# xns-ip67-ESP12.net
KiCad netlist of a schematic drawn in EAGLE
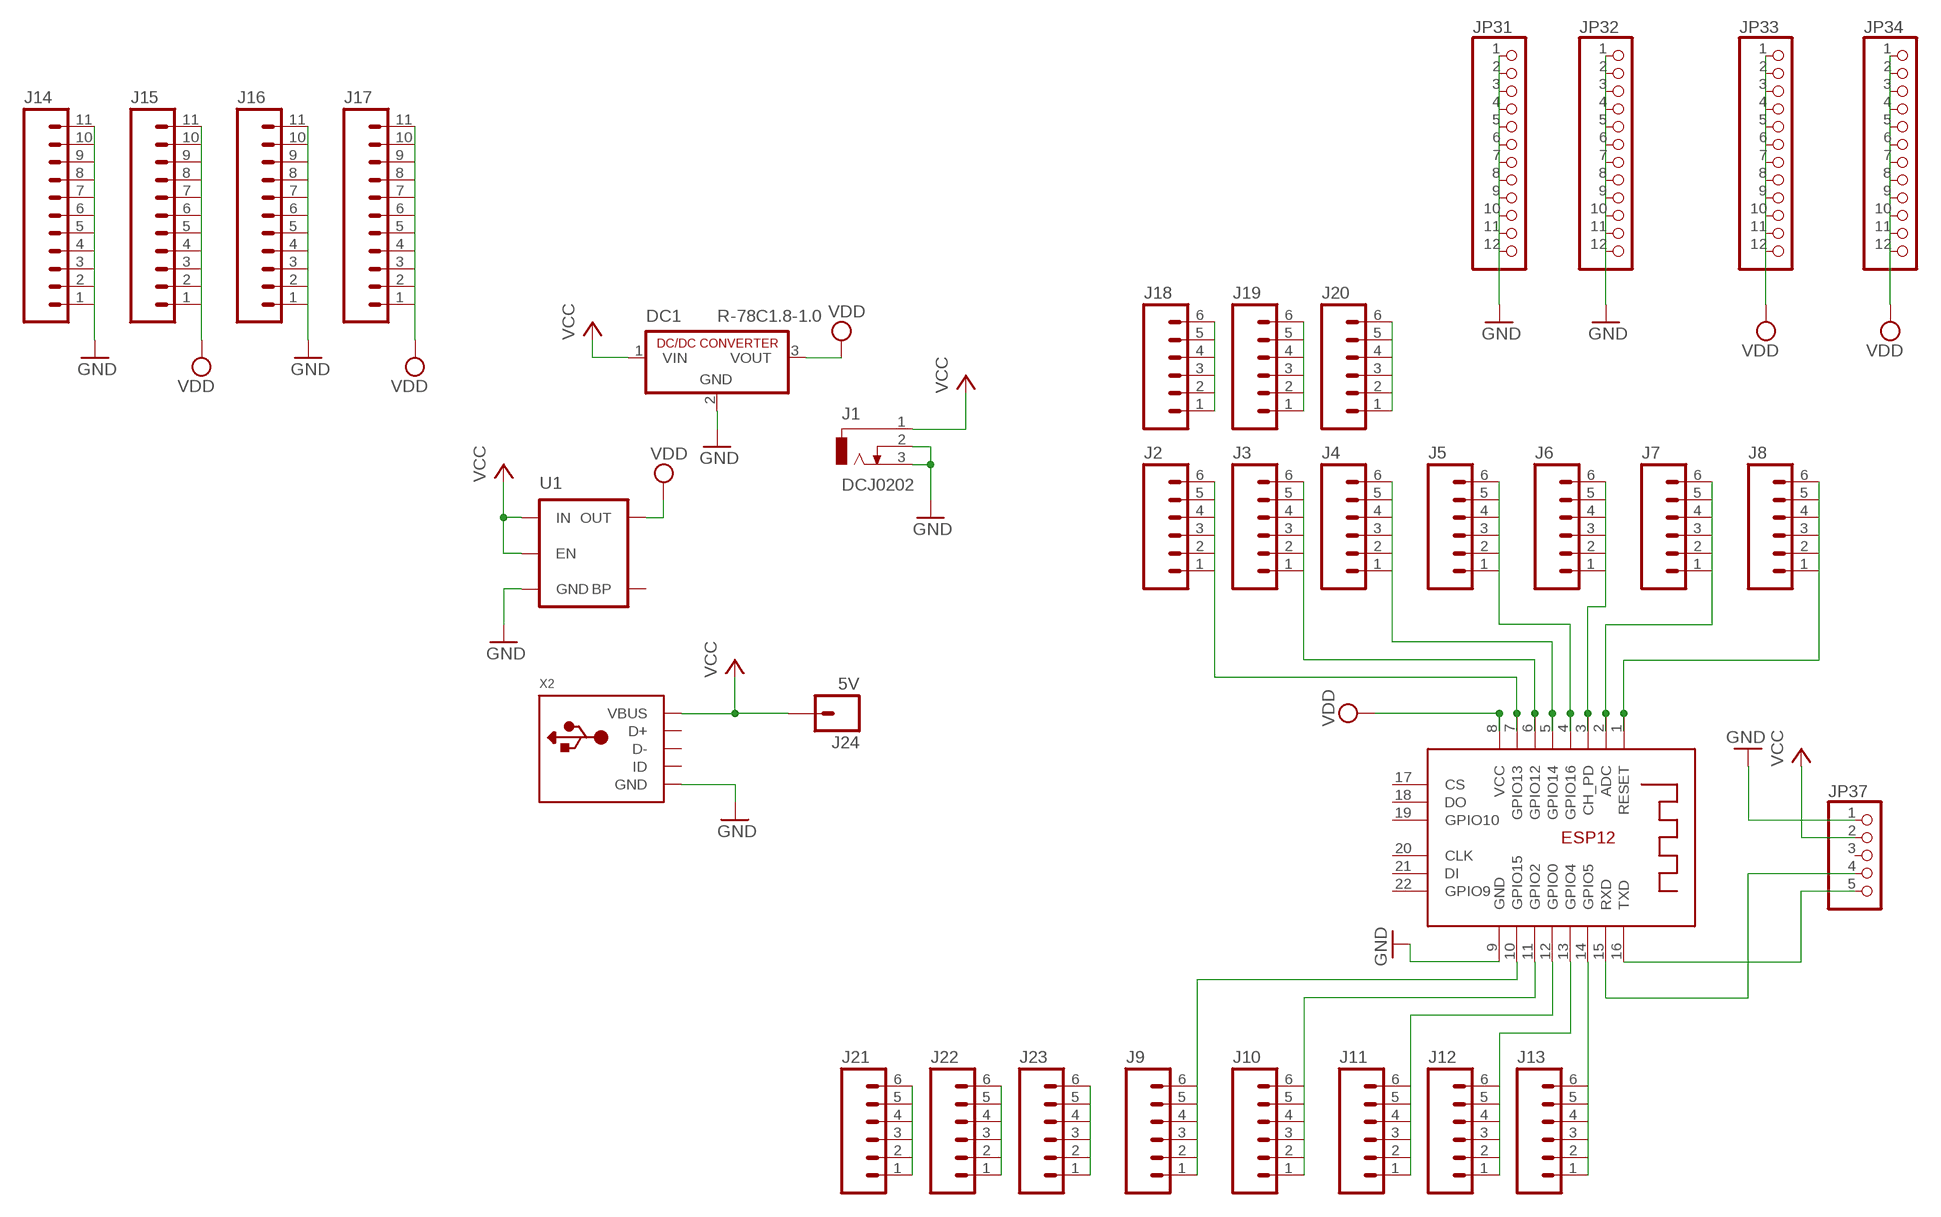
[diagram p0: schematic, sheet 1, part 1 of 2]
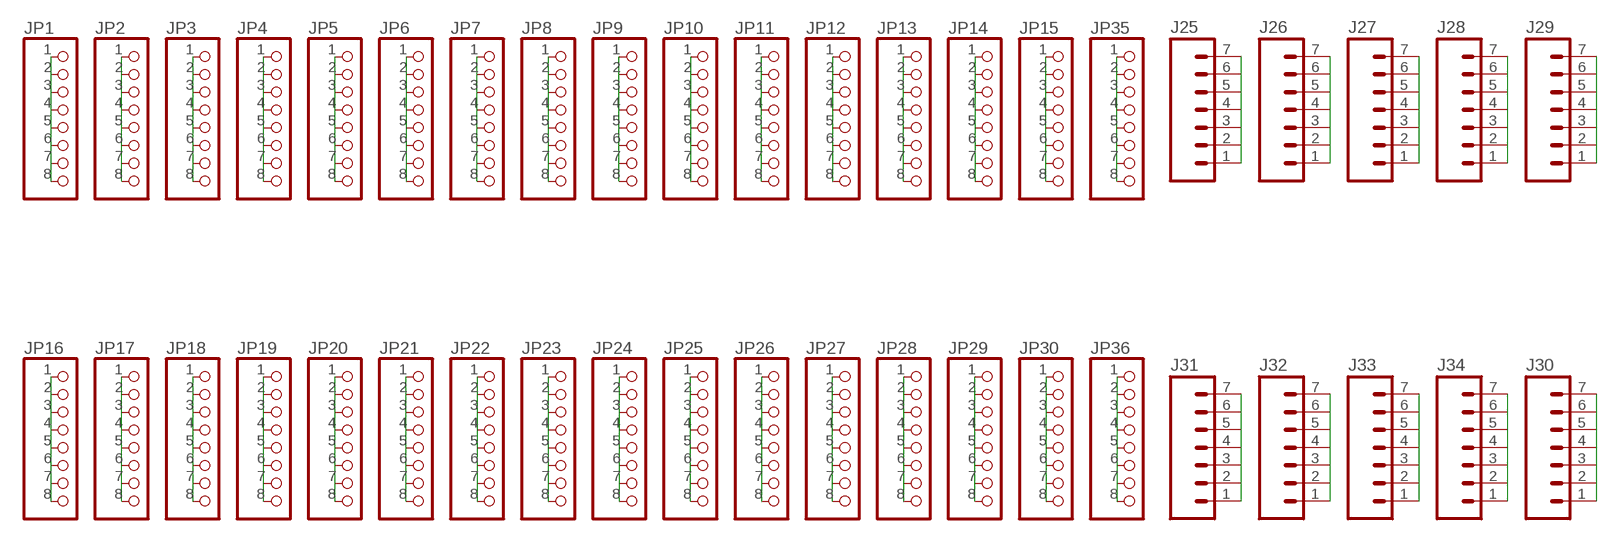
[diagram p1: schematic, sheet 1, part 2 of 2]

(export (version "E")
  (design (tool "Eeschema 10.0.6"))
  (components
    (comp (ref "DC1")
      (value "R-78C1.8-1.0")
      (footprint "eagle-import:SIP3")
      (libsource (lib "eagle-import") (part "R-78C-1.01.8"))
    )
    (comp (ref "J1")
      (value "DCJ0202")
      (footprint "eagle-import:DCJ0202")
      (libsource (lib "eagle-import") (part "DCJ0202"))
    )
    (comp (ref "J2")
      (value "M06NO_SILK_FEMALE_PTH")
      (footprint "eagle-import:1X06_NO_SILK")
      (libsource (lib "eagle-import") (part "M06NO_SILK_FEMALE_PTH"))
    )
    (comp (ref "J3")
      (value "M06NO_SILK_FEMALE_PTH")
      (footprint "eagle-import:1X06_NO_SILK")
      (libsource (lib "eagle-import") (part "M06NO_SILK_FEMALE_PTH"))
    )
    (comp (ref "J4")
      (value "M06NO_SILK_FEMALE_PTH")
      (footprint "eagle-import:1X06_NO_SILK")
      (libsource (lib "eagle-import") (part "M06NO_SILK_FEMALE_PTH"))
    )
    (comp (ref "J5")
      (value "M06NO_SILK_FEMALE_PTH")
      (footprint "eagle-import:1X06_NO_SILK")
      (libsource (lib "eagle-import") (part "M06NO_SILK_FEMALE_PTH"))
    )
    (comp (ref "J6")
      (value "M06NO_SILK_FEMALE_PTH")
      (footprint "eagle-import:1X06_NO_SILK")
      (libsource (lib "eagle-import") (part "M06NO_SILK_FEMALE_PTH"))
    )
    (comp (ref "J7")
      (value "M06NO_SILK_FEMALE_PTH")
      (footprint "eagle-import:1X06_NO_SILK")
      (libsource (lib "eagle-import") (part "M06NO_SILK_FEMALE_PTH"))
    )
    (comp (ref "J8")
      (value "M06NO_SILK_FEMALE_PTH")
      (footprint "eagle-import:1X06_NO_SILK")
      (libsource (lib "eagle-import") (part "M06NO_SILK_FEMALE_PTH"))
    )
    (comp (ref "J9")
      (value "M06NO_SILK_FEMALE_PTH")
      (footprint "eagle-import:1X06_NO_SILK")
      (libsource (lib "eagle-import") (part "M06NO_SILK_FEMALE_PTH"))
    )
    (comp (ref "J10")
      (value "M06NO_SILK_FEMALE_PTH")
      (footprint "eagle-import:1X06_NO_SILK")
      (libsource (lib "eagle-import") (part "M06NO_SILK_FEMALE_PTH"))
    )
    (comp (ref "J11")
      (value "M06NO_SILK_FEMALE_PTH")
      (footprint "eagle-import:1X06_NO_SILK")
      (libsource (lib "eagle-import") (part "M06NO_SILK_FEMALE_PTH"))
    )
    (comp (ref "J12")
      (value "M06NO_SILK_FEMALE_PTH")
      (footprint "eagle-import:1X06_NO_SILK")
      (libsource (lib "eagle-import") (part "M06NO_SILK_FEMALE_PTH"))
    )
    (comp (ref "J13")
      (value "M06NO_SILK_FEMALE_PTH")
      (footprint "eagle-import:1X06_NO_SILK")
      (libsource (lib "eagle-import") (part "M06NO_SILK_FEMALE_PTH"))
    )
    (comp (ref "J14")
      (value "M111X11_NO_SILK")
      (footprint "eagle-import:1X11_NO_SILK")
      (libsource (lib "eagle-import") (part "M111X11_NO_SILK"))
    )
    (comp (ref "J15")
      (value "M111X11_NO_SILK")
      (footprint "eagle-import:1X11_NO_SILK")
      (libsource (lib "eagle-import") (part "M111X11_NO_SILK"))
    )
    (comp (ref "J16")
      (value "M111X11_NO_SILK")
      (footprint "eagle-import:1X11_NO_SILK")
      (libsource (lib "eagle-import") (part "M111X11_NO_SILK"))
    )
    (comp (ref "J17")
      (value "M111X11_NO_SILK")
      (footprint "eagle-import:1X11_NO_SILK")
      (libsource (lib "eagle-import") (part "M111X11_NO_SILK"))
    )
    (comp (ref "J18")
      (value "M06NO_SILK_FEMALE_PTH")
      (footprint "eagle-import:1X06_NO_SILK")
      (libsource (lib "eagle-import") (part "M06NO_SILK_FEMALE_PTH"))
    )
    (comp (ref "J19")
      (value "M06NO_SILK_FEMALE_PTH")
      (footprint "eagle-import:1X06_NO_SILK")
      (libsource (lib "eagle-import") (part "M06NO_SILK_FEMALE_PTH"))
    )
    (comp (ref "J20")
      (value "M06NO_SILK_FEMALE_PTH")
      (footprint "eagle-import:1X06_NO_SILK")
      (libsource (lib "eagle-import") (part "M06NO_SILK_FEMALE_PTH"))
    )
    (comp (ref "J21")
      (value "M06NO_SILK_FEMALE_PTH")
      (footprint "eagle-import:1X06_NO_SILK")
      (libsource (lib "eagle-import") (part "M06NO_SILK_FEMALE_PTH"))
    )
    (comp (ref "J22")
      (value "M06NO_SILK_FEMALE_PTH")
      (footprint "eagle-import:1X06_NO_SILK")
      (libsource (lib "eagle-import") (part "M06NO_SILK_FEMALE_PTH"))
    )
    (comp (ref "J23")
      (value "M06NO_SILK_FEMALE_PTH")
      (footprint "eagle-import:1X06_NO_SILK")
      (libsource (lib "eagle-import") (part "M06NO_SILK_FEMALE_PTH"))
    )
    (comp (ref "J24")
      (value "5V")
      (footprint "eagle-import:1X01_NO_SILK")
      (libsource (lib "eagle-import") (part "M01PTH_NO_SILK_YES_STOP"))
    )
    (comp (ref "J25")
      (value "M07NO_SILK")
      (footprint "eagle-import:1X07_NO_SILK")
      (libsource (lib "eagle-import") (part "M07NO_SILK"))
    )
    (comp (ref "J26")
      (value "M07NO_SILK")
      (footprint "eagle-import:1X07_NO_SILK")
      (libsource (lib "eagle-import") (part "M07NO_SILK"))
    )
    (comp (ref "J27")
      (value "M07NO_SILK")
      (footprint "eagle-import:1X07_NO_SILK")
      (libsource (lib "eagle-import") (part "M07NO_SILK"))
    )
    (comp (ref "J28")
      (value "M07NO_SILK")
      (footprint "eagle-import:1X07_NO_SILK")
      (libsource (lib "eagle-import") (part "M07NO_SILK"))
    )
    (comp (ref "J29")
      (value "M07NO_SILK")
      (footprint "eagle-import:1X07_NO_SILK")
      (libsource (lib "eagle-import") (part "M07NO_SILK"))
    )
    (comp (ref "J30")
      (value "M07NO_SILK")
      (footprint "eagle-import:1X07_NO_SILK")
      (libsource (lib "eagle-import") (part "M07NO_SILK"))
    )
    (comp (ref "J31")
      (value "M07NO_SILK")
      (footprint "eagle-import:1X07_NO_SILK")
      (libsource (lib "eagle-import") (part "M07NO_SILK"))
    )
    (comp (ref "J32")
      (value "M07NO_SILK")
      (footprint "eagle-import:1X07_NO_SILK")
      (libsource (lib "eagle-import") (part "M07NO_SILK"))
    )
    (comp (ref "J33")
      (value "M07NO_SILK")
      (footprint "eagle-import:1X07_NO_SILK")
      (libsource (lib "eagle-import") (part "M07NO_SILK"))
    )
    (comp (ref "J34")
      (value "M07NO_SILK")
      (footprint "eagle-import:1X07_NO_SILK")
      (libsource (lib "eagle-import") (part "M07NO_SILK"))
    )
    (comp (ref "JP1")
      (value "PINHD-1X8CLEANBIG")
      (footprint "eagle-import:1X08-CLEANBIG")
      (libsource (lib "eagle-import") (part "PINHD-1X8CLEANBIG"))
    )
    (comp (ref "JP2")
      (value "PINHD-1X8CLEANBIG")
      (footprint "eagle-import:1X08-CLEANBIG")
      (libsource (lib "eagle-import") (part "PINHD-1X8CLEANBIG"))
    )
    (comp (ref "JP3")
      (value "PINHD-1X8CLEANBIG")
      (footprint "eagle-import:1X08-CLEANBIG")
      (libsource (lib "eagle-import") (part "PINHD-1X8CLEANBIG"))
    )
    (comp (ref "JP4")
      (value "PINHD-1X8CLEANBIG")
      (footprint "eagle-import:1X08-CLEANBIG")
      (libsource (lib "eagle-import") (part "PINHD-1X8CLEANBIG"))
    )
    (comp (ref "JP5")
      (value "PINHD-1X8CLEANBIG")
      (footprint "eagle-import:1X08-CLEANBIG")
      (libsource (lib "eagle-import") (part "PINHD-1X8CLEANBIG"))
    )
    (comp (ref "JP6")
      (value "PINHD-1X8CLEANBIG")
      (footprint "eagle-import:1X08-CLEANBIG")
      (libsource (lib "eagle-import") (part "PINHD-1X8CLEANBIG"))
    )
    (comp (ref "JP7")
      (value "PINHD-1X8CLEANBIG")
      (footprint "eagle-import:1X08-CLEANBIG")
      (libsource (lib "eagle-import") (part "PINHD-1X8CLEANBIG"))
    )
    (comp (ref "JP8")
      (value "PINHD-1X8CLEANBIG")
      (footprint "eagle-import:1X08-CLEANBIG")
      (libsource (lib "eagle-import") (part "PINHD-1X8CLEANBIG"))
    )
    (comp (ref "JP9")
      (value "PINHD-1X8CLEANBIG")
      (footprint "eagle-import:1X08-CLEANBIG")
      (libsource (lib "eagle-import") (part "PINHD-1X8CLEANBIG"))
    )
    (comp (ref "JP10")
      (value "PINHD-1X8CLEANBIG")
      (footprint "eagle-import:1X08-CLEANBIG")
      (libsource (lib "eagle-import") (part "PINHD-1X8CLEANBIG"))
    )
    (comp (ref "JP11")
      (value "PINHD-1X8CLEANBIG")
      (footprint "eagle-import:1X08-CLEANBIG")
      (libsource (lib "eagle-import") (part "PINHD-1X8CLEANBIG"))
    )
    (comp (ref "JP12")
      (value "PINHD-1X8CLEANBIG")
      (footprint "eagle-import:1X08-CLEANBIG")
      (libsource (lib "eagle-import") (part "PINHD-1X8CLEANBIG"))
    )
    (comp (ref "JP13")
      (value "PINHD-1X8CLEANBIG")
      (footprint "eagle-import:1X08-CLEANBIG")
      (libsource (lib "eagle-import") (part "PINHD-1X8CLEANBIG"))
    )
    (comp (ref "JP14")
      (value "PINHD-1X8CLEANBIG")
      (footprint "eagle-import:1X08-CLEANBIG")
      (libsource (lib "eagle-import") (part "PINHD-1X8CLEANBIG"))
    )
    (comp (ref "JP15")
      (value "PINHD-1X8CLEANBIG")
      (footprint "eagle-import:1X08-CLEANBIG")
      (libsource (lib "eagle-import") (part "PINHD-1X8CLEANBIG"))
    )
    (comp (ref "JP16")
      (value "PINHD-1X8CLEANBIG")
      (footprint "eagle-import:1X08-CLEANBIG")
      (libsource (lib "eagle-import") (part "PINHD-1X8CLEANBIG"))
    )
    (comp (ref "JP17")
      (value "PINHD-1X8CLEANBIG")
      (footprint "eagle-import:1X08-CLEANBIG")
      (libsource (lib "eagle-import") (part "PINHD-1X8CLEANBIG"))
    )
    (comp (ref "JP18")
      (value "PINHD-1X8CLEANBIG")
      (footprint "eagle-import:1X08-CLEANBIG")
      (libsource (lib "eagle-import") (part "PINHD-1X8CLEANBIG"))
    )
    (comp (ref "JP19")
      (value "PINHD-1X8CLEANBIG")
      (footprint "eagle-import:1X08-CLEANBIG")
      (libsource (lib "eagle-import") (part "PINHD-1X8CLEANBIG"))
    )
    (comp (ref "JP20")
      (value "PINHD-1X8CLEANBIG")
      (footprint "eagle-import:1X08-CLEANBIG")
      (libsource (lib "eagle-import") (part "PINHD-1X8CLEANBIG"))
    )
    (comp (ref "JP21")
      (value "PINHD-1X8CLEANBIG")
      (footprint "eagle-import:1X08-CLEANBIG")
      (libsource (lib "eagle-import") (part "PINHD-1X8CLEANBIG"))
    )
    (comp (ref "JP22")
      (value "PINHD-1X8CLEANBIG")
      (footprint "eagle-import:1X08-CLEANBIG")
      (libsource (lib "eagle-import") (part "PINHD-1X8CLEANBIG"))
    )
    (comp (ref "JP23")
      (value "PINHD-1X8CLEANBIG")
      (footprint "eagle-import:1X08-CLEANBIG")
      (libsource (lib "eagle-import") (part "PINHD-1X8CLEANBIG"))
    )
    (comp (ref "JP24")
      (value "PINHD-1X8CLEANBIG")
      (footprint "eagle-import:1X08-CLEANBIG")
      (libsource (lib "eagle-import") (part "PINHD-1X8CLEANBIG"))
    )
    (comp (ref "JP25")
      (value "PINHD-1X8CLEANBIG")
      (footprint "eagle-import:1X08-CLEANBIG")
      (libsource (lib "eagle-import") (part "PINHD-1X8CLEANBIG"))
    )
    (comp (ref "JP26")
      (value "PINHD-1X8CLEANBIG")
      (footprint "eagle-import:1X08-CLEANBIG")
      (libsource (lib "eagle-import") (part "PINHD-1X8CLEANBIG"))
    )
    (comp (ref "JP27")
      (value "PINHD-1X8CLEANBIG")
      (footprint "eagle-import:1X08-CLEANBIG")
      (libsource (lib "eagle-import") (part "PINHD-1X8CLEANBIG"))
    )
    (comp (ref "JP28")
      (value "PINHD-1X8CLEANBIG")
      (footprint "eagle-import:1X08-CLEANBIG")
      (libsource (lib "eagle-import") (part "PINHD-1X8CLEANBIG"))
    )
    (comp (ref "JP29")
      (value "PINHD-1X8CLEANBIG")
      (footprint "eagle-import:1X08-CLEANBIG")
      (libsource (lib "eagle-import") (part "PINHD-1X8CLEANBIG"))
    )
    (comp (ref "JP30")
      (value "PINHD-1X8CLEANBIG")
      (footprint "eagle-import:1X08-CLEANBIG")
      (libsource (lib "eagle-import") (part "PINHD-1X8CLEANBIG"))
    )
    (comp (ref "JP31")
      (value "HEADER-1X12")
      (footprint "eagle-import:1X12_ROUND")
      (libsource (lib "eagle-import") (part "HEADER-1X12"))
    )
    (comp (ref "JP32")
      (value "HEADER-1X12")
      (footprint "eagle-import:1X12_ROUND")
      (libsource (lib "eagle-import") (part "HEADER-1X12"))
    )
    (comp (ref "JP33")
      (value "HEADER-1X12")
      (footprint "eagle-import:1X12_ROUND")
      (libsource (lib "eagle-import") (part "HEADER-1X12"))
    )
    (comp (ref "JP34")
      (value "HEADER-1X12")
      (footprint "eagle-import:1X12_ROUND")
      (libsource (lib "eagle-import") (part "HEADER-1X12"))
    )
    (comp (ref "JP35")
      (value "PINHD-1X8CLEANBIG")
      (footprint "eagle-import:1X08-CLEANBIG")
      (libsource (lib "eagle-import") (part "PINHD-1X8CLEANBIG"))
    )
    (comp (ref "JP36")
      (value "PINHD-1X8CLEANBIG")
      (footprint "eagle-import:1X08-CLEANBIG")
      (libsource (lib "eagle-import") (part "PINHD-1X8CLEANBIG"))
    )
    (comp (ref "JP37")
      (value "PINHD-1X5")
      (footprint "eagle-import:1X05")
      (libsource (lib "eagle-import") (part "PINHD-1X5"))
    )
    (comp (ref "U1")
      (value "MIC52053.3V")
      (footprint "eagle-import:SOT23-5")
      (libsource (lib "eagle-import") (part "MIC52053.3V"))
    )
    (comp (ref "X1")
      (value "ESP-12E")
      (footprint "eagle-import:ESP-12E")
      (libsource (lib "eagle-import") (part "ESP-12E"))
    )
    (comp (ref "X2")
      (value "USBMICRO_20329")
      (footprint "eagle-import:4UCONN_20329")
      (libsource (lib "eagle-import") (part "USBMICRO_20329"))
    )
  )
  (nets
    (net (code "1") (name "GND") (class "Default")
      (node (ref "DC1") (pin "2") (pinfunction "GND_2") (pintype "passive"))
      (node (ref "J1") (pin "2") (pinfunction "2_2") (pintype "passive"))
      (node (ref "J1") (pin "3") (pinfunction "3_3") (pintype "passive"))
      (node (ref "J14") (pin "1") (pinfunction "1_1") (pintype "passive"))
      (node (ref "J14") (pin "10") (pinfunction "10_10") (pintype "passive"))
      (node (ref "J14") (pin "11") (pinfunction "11_11") (pintype "passive"))
      (node (ref "J14") (pin "2") (pinfunction "2_2") (pintype "passive"))
      (node (ref "J14") (pin "3") (pinfunction "3_3") (pintype "passive"))
      (node (ref "J14") (pin "4") (pinfunction "4_4") (pintype "passive"))
      (node (ref "J14") (pin "5") (pinfunction "5_5") (pintype "passive"))
      (node (ref "J14") (pin "6") (pinfunction "6_6") (pintype "passive"))
      (node (ref "J14") (pin "7") (pinfunction "7_7") (pintype "passive"))
      (node (ref "J14") (pin "8") (pinfunction "8_8") (pintype "passive"))
      (node (ref "J14") (pin "9") (pinfunction "9_9") (pintype "passive"))
      (node (ref "J16") (pin "1") (pinfunction "1_1") (pintype "passive"))
      (node (ref "J16") (pin "10") (pinfunction "10_10") (pintype "passive"))
      (node (ref "J16") (pin "11") (pinfunction "11_11") (pintype "passive"))
      (node (ref "J16") (pin "2") (pinfunction "2_2") (pintype "passive"))
      (node (ref "J16") (pin "3") (pinfunction "3_3") (pintype "passive"))
      (node (ref "J16") (pin "4") (pinfunction "4_4") (pintype "passive"))
      (node (ref "J16") (pin "5") (pinfunction "5_5") (pintype "passive"))
      (node (ref "J16") (pin "6") (pinfunction "6_6") (pintype "passive"))
      (node (ref "J16") (pin "7") (pinfunction "7_7") (pintype "passive"))
      (node (ref "J16") (pin "8") (pinfunction "8_8") (pintype "passive"))
      (node (ref "J16") (pin "9") (pinfunction "9_9") (pintype "passive"))
      (node (ref "JP31") (pin "1") (pinfunction "1_1") (pintype "passive"))
      (node (ref "JP31") (pin "10") (pinfunction "10_10") (pintype "passive"))
      (node (ref "JP31") (pin "11") (pinfunction "11_11") (pintype "passive"))
      (node (ref "JP31") (pin "12") (pinfunction "12_12") (pintype "passive"))
      (node (ref "JP31") (pin "2") (pinfunction "2_2") (pintype "passive"))
      (node (ref "JP31") (pin "3") (pinfunction "3_3") (pintype "passive"))
      (node (ref "JP31") (pin "4") (pinfunction "4_4") (pintype "passive"))
      (node (ref "JP31") (pin "5") (pinfunction "5_5") (pintype "passive"))
      (node (ref "JP31") (pin "6") (pinfunction "6_6") (pintype "passive"))
      (node (ref "JP31") (pin "7") (pinfunction "7_7") (pintype "passive"))
      (node (ref "JP31") (pin "8") (pinfunction "8_8") (pintype "passive"))
      (node (ref "JP31") (pin "9") (pinfunction "9_9") (pintype "passive"))
      (node (ref "JP32") (pin "1") (pinfunction "1_1") (pintype "passive"))
      (node (ref "JP32") (pin "10") (pinfunction "10_10") (pintype "passive"))
      (node (ref "JP32") (pin "11") (pinfunction "11_11") (pintype "passive"))
      (node (ref "JP32") (pin "12") (pinfunction "12_12") (pintype "passive"))
      (node (ref "JP32") (pin "2") (pinfunction "2_2") (pintype "passive"))
      (node (ref "JP32") (pin "3") (pinfunction "3_3") (pintype "passive"))
      (node (ref "JP32") (pin "4") (pinfunction "4_4") (pintype "passive"))
      (node (ref "JP32") (pin "5") (pinfunction "5_5") (pintype "passive"))
      (node (ref "JP32") (pin "6") (pinfunction "6_6") (pintype "passive"))
      (node (ref "JP32") (pin "7") (pinfunction "7_7") (pintype "passive"))
      (node (ref "JP32") (pin "8") (pinfunction "8_8") (pintype "passive"))
      (node (ref "JP32") (pin "9") (pinfunction "9_9") (pintype "passive"))
      (node (ref "JP37") (pin "1") (pinfunction "1_1") (pintype "passive"))
      (node (ref "U1") (pin "2") (pinfunction "GND_2") (pintype "input"))
      (node (ref "X1") (pin "9") (pinfunction "GND_9") (pintype "power_in"))
      (node (ref "X2") (pin "BASE@1") (pinfunction "GND_BASE@1") (pintype "power_in"))
      (node (ref "X2") (pin "BASE@2") (pinfunction "GND_BASE@2") (pintype "power_in"))
      (node (ref "X2") (pin "GND") (pinfunction "GND_GND") (pintype "power_in"))
      (node (ref "X2") (pin "SPRT@1") (pinfunction "GND_SPRT@1") (pintype "power_in"))
      (node (ref "X2") (pin "SPRT@2") (pinfunction "GND_SPRT@2") (pintype "power_in"))
      (node (ref "X2") (pin "SPRT@3") (pinfunction "GND_SPRT@3") (pintype "power_in"))
      (node (ref "X2") (pin "SPRT@4") (pinfunction "GND_SPRT@4") (pintype "power_in"))
    )
    (net (code "2") (name "Net-(J18-Pad1)") (class "Default")
      (node (ref "J18") (pin "1") (pinfunction "1_1") (pintype "passive"))
      (node (ref "J18") (pin "2") (pinfunction "2_2") (pintype "passive"))
      (node (ref "J18") (pin "3") (pinfunction "3_3") (pintype "passive"))
      (node (ref "J18") (pin "4") (pinfunction "4_4") (pintype "passive"))
      (node (ref "J18") (pin "5") (pinfunction "5_5") (pintype "passive"))
      (node (ref "J18") (pin "6") (pinfunction "6_6") (pintype "passive"))
    )
    (net (code "3") (name "Net-(J19-Pad1)") (class "Default")
      (node (ref "J19") (pin "1") (pinfunction "1_1") (pintype "passive"))
      (node (ref "J19") (pin "2") (pinfunction "2_2") (pintype "passive"))
      (node (ref "J19") (pin "3") (pinfunction "3_3") (pintype "passive"))
      (node (ref "J19") (pin "4") (pinfunction "4_4") (pintype "passive"))
      (node (ref "J19") (pin "5") (pinfunction "5_5") (pintype "passive"))
      (node (ref "J19") (pin "6") (pinfunction "6_6") (pintype "passive"))
    )
    (net (code "4") (name "Net-(J20-Pad1)") (class "Default")
      (node (ref "J20") (pin "1") (pinfunction "1_1") (pintype "passive"))
      (node (ref "J20") (pin "2") (pinfunction "2_2") (pintype "passive"))
      (node (ref "J20") (pin "3") (pinfunction "3_3") (pintype "passive"))
      (node (ref "J20") (pin "4") (pinfunction "4_4") (pintype "passive"))
      (node (ref "J20") (pin "5") (pinfunction "5_5") (pintype "passive"))
      (node (ref "J20") (pin "6") (pinfunction "6_6") (pintype "passive"))
    )
    (net (code "5") (name "Net-(J21-Pad1)") (class "Default")
      (node (ref "J21") (pin "1") (pinfunction "1_1") (pintype "passive"))
      (node (ref "J21") (pin "2") (pinfunction "2_2") (pintype "passive"))
      (node (ref "J21") (pin "3") (pinfunction "3_3") (pintype "passive"))
      (node (ref "J21") (pin "4") (pinfunction "4_4") (pintype "passive"))
      (node (ref "J21") (pin "5") (pinfunction "5_5") (pintype "passive"))
      (node (ref "J21") (pin "6") (pinfunction "6_6") (pintype "passive"))
    )
    (net (code "6") (name "Net-(J22-Pad1)") (class "Default")
      (node (ref "J22") (pin "1") (pinfunction "1_1") (pintype "passive"))
      (node (ref "J22") (pin "2") (pinfunction "2_2") (pintype "passive"))
      (node (ref "J22") (pin "3") (pinfunction "3_3") (pintype "passive"))
      (node (ref "J22") (pin "4") (pinfunction "4_4") (pintype "passive"))
      (node (ref "J22") (pin "5") (pinfunction "5_5") (pintype "passive"))
      (node (ref "J22") (pin "6") (pinfunction "6_6") (pintype "passive"))
    )
    (net (code "7") (name "Net-(J23-Pad1)") (class "Default")
      (node (ref "J23") (pin "1") (pinfunction "1_1") (pintype "passive"))
      (node (ref "J23") (pin "2") (pinfunction "2_2") (pintype "passive"))
      (node (ref "J23") (pin "3") (pinfunction "3_3") (pintype "passive"))
      (node (ref "J23") (pin "4") (pinfunction "4_4") (pintype "passive"))
      (node (ref "J23") (pin "5") (pinfunction "5_5") (pintype "passive"))
      (node (ref "J23") (pin "6") (pinfunction "6_6") (pintype "passive"))
    )
    (net (code "8") (name "Net-(J25-Pad1)") (class "Default")
      (node (ref "J25") (pin "1") (pinfunction "1_1") (pintype "passive"))
      (node (ref "J25") (pin "2") (pinfunction "2_2") (pintype "passive"))
      (node (ref "J25") (pin "3") (pinfunction "3_3") (pintype "passive"))
      (node (ref "J25") (pin "4") (pinfunction "4_4") (pintype "passive"))
      (node (ref "J25") (pin "5") (pinfunction "5_5") (pintype "passive"))
      (node (ref "J25") (pin "6") (pinfunction "6_6") (pintype "passive"))
      (node (ref "J25") (pin "7") (pinfunction "7_7") (pintype "passive"))
    )
    (net (code "9") (name "Net-(J26-Pad1)") (class "Default")
      (node (ref "J26") (pin "1") (pinfunction "1_1") (pintype "passive"))
      (node (ref "J26") (pin "2") (pinfunction "2_2") (pintype "passive"))
      (node (ref "J26") (pin "3") (pinfunction "3_3") (pintype "passive"))
      (node (ref "J26") (pin "4") (pinfunction "4_4") (pintype "passive"))
      (node (ref "J26") (pin "5") (pinfunction "5_5") (pintype "passive"))
      (node (ref "J26") (pin "6") (pinfunction "6_6") (pintype "passive"))
      (node (ref "J26") (pin "7") (pinfunction "7_7") (pintype "passive"))
    )
    (net (code "10") (name "Net-(J27-Pad1)") (class "Default")
      (node (ref "J27") (pin "1") (pinfunction "1_1") (pintype "passive"))
      (node (ref "J27") (pin "2") (pinfunction "2_2") (pintype "passive"))
      (node (ref "J27") (pin "3") (pinfunction "3_3") (pintype "passive"))
      (node (ref "J27") (pin "4") (pinfunction "4_4") (pintype "passive"))
      (node (ref "J27") (pin "5") (pinfunction "5_5") (pintype "passive"))
      (node (ref "J27") (pin "6") (pinfunction "6_6") (pintype "passive"))
      (node (ref "J27") (pin "7") (pinfunction "7_7") (pintype "passive"))
    )
    (net (code "11") (name "Net-(J28-Pad1)") (class "Default")
      (node (ref "J28") (pin "1") (pinfunction "1_1") (pintype "passive"))
      (node (ref "J28") (pin "2") (pinfunction "2_2") (pintype "passive"))
      (node (ref "J28") (pin "3") (pinfunction "3_3") (pintype "passive"))
      (node (ref "J28") (pin "4") (pinfunction "4_4") (pintype "passive"))
      (node (ref "J28") (pin "5") (pinfunction "5_5") (pintype "passive"))
      (node (ref "J28") (pin "6") (pinfunction "6_6") (pintype "passive"))
      (node (ref "J28") (pin "7") (pinfunction "7_7") (pintype "passive"))
    )
    (net (code "12") (name "Net-(J29-Pad1)") (class "Default")
      (node (ref "J29") (pin "1") (pinfunction "1_1") (pintype "passive"))
      (node (ref "J29") (pin "2") (pinfunction "2_2") (pintype "passive"))
      (node (ref "J29") (pin "3") (pinfunction "3_3") (pintype "passive"))
      (node (ref "J29") (pin "4") (pinfunction "4_4") (pintype "passive"))
      (node (ref "J29") (pin "5") (pinfunction "5_5") (pintype "passive"))
      (node (ref "J29") (pin "6") (pinfunction "6_6") (pintype "passive"))
      (node (ref "J29") (pin "7") (pinfunction "7_7") (pintype "passive"))
    )
    (net (code "13") (name "Net-(J30-Pad1)") (class "Default")
      (node (ref "J30") (pin "1") (pinfunction "1_1") (pintype "passive"))
      (node (ref "J30") (pin "2") (pinfunction "2_2") (pintype "passive"))
      (node (ref "J30") (pin "3") (pinfunction "3_3") (pintype "passive"))
      (node (ref "J30") (pin "4") (pinfunction "4_4") (pintype "passive"))
      (node (ref "J30") (pin "5") (pinfunction "5_5") (pintype "passive"))
      (node (ref "J30") (pin "6") (pinfunction "6_6") (pintype "passive"))
      (node (ref "J30") (pin "7") (pinfunction "7_7") (pintype "passive"))
    )
    (net (code "14") (name "Net-(J31-Pad1)") (class "Default")
      (node (ref "J31") (pin "1") (pinfunction "1_1") (pintype "passive"))
      (node (ref "J31") (pin "2") (pinfunction "2_2") (pintype "passive"))
      (node (ref "J31") (pin "3") (pinfunction "3_3") (pintype "passive"))
      (node (ref "J31") (pin "4") (pinfunction "4_4") (pintype "passive"))
      (node (ref "J31") (pin "5") (pinfunction "5_5") (pintype "passive"))
      (node (ref "J31") (pin "6") (pinfunction "6_6") (pintype "passive"))
      (node (ref "J31") (pin "7") (pinfunction "7_7") (pintype "passive"))
    )
    (net (code "15") (name "Net-(J32-Pad1)") (class "Default")
      (node (ref "J32") (pin "1") (pinfunction "1_1") (pintype "passive"))
      (node (ref "J32") (pin "2") (pinfunction "2_2") (pintype "passive"))
      (node (ref "J32") (pin "3") (pinfunction "3_3") (pintype "passive"))
      (node (ref "J32") (pin "4") (pinfunction "4_4") (pintype "passive"))
      (node (ref "J32") (pin "5") (pinfunction "5_5") (pintype "passive"))
      (node (ref "J32") (pin "6") (pinfunction "6_6") (pintype "passive"))
      (node (ref "J32") (pin "7") (pinfunction "7_7") (pintype "passive"))
    )
    (net (code "16") (name "Net-(J33-Pad1)") (class "Default")
      (node (ref "J33") (pin "1") (pinfunction "1_1") (pintype "passive"))
      (node (ref "J33") (pin "2") (pinfunction "2_2") (pintype "passive"))
      (node (ref "J33") (pin "3") (pinfunction "3_3") (pintype "passive"))
      (node (ref "J33") (pin "4") (pinfunction "4_4") (pintype "passive"))
      (node (ref "J33") (pin "5") (pinfunction "5_5") (pintype "passive"))
      (node (ref "J33") (pin "6") (pinfunction "6_6") (pintype "passive"))
      (node (ref "J33") (pin "7") (pinfunction "7_7") (pintype "passive"))
    )
    (net (code "17") (name "Net-(J34-Pad1)") (class "Default")
      (node (ref "J34") (pin "1") (pinfunction "1_1") (pintype "passive"))
      (node (ref "J34") (pin "2") (pinfunction "2_2") (pintype "passive"))
      (node (ref "J34") (pin "3") (pinfunction "3_3") (pintype "passive"))
      (node (ref "J34") (pin "4") (pinfunction "4_4") (pintype "passive"))
      (node (ref "J34") (pin "5") (pinfunction "5_5") (pintype "passive"))
      (node (ref "J34") (pin "6") (pinfunction "6_6") (pintype "passive"))
      (node (ref "J34") (pin "7") (pinfunction "7_7") (pintype "passive"))
    )
    (net (code "18") (name "Net-(JP1-Pad1)") (class "Default")
      (node (ref "JP1") (pin "1") (pinfunction "1_1") (pintype "passive"))
      (node (ref "JP1") (pin "2") (pinfunction "2_2") (pintype "passive"))
      (node (ref "JP1") (pin "3") (pinfunction "3_3") (pintype "passive"))
      (node (ref "JP1") (pin "4") (pinfunction "4_4") (pintype "passive"))
      (node (ref "JP1") (pin "5") (pinfunction "5_5") (pintype "passive"))
      (node (ref "JP1") (pin "6") (pinfunction "6_6") (pintype "passive"))
      (node (ref "JP1") (pin "7") (pinfunction "7_7") (pintype "passive"))
      (node (ref "JP1") (pin "8") (pinfunction "8_8") (pintype "passive"))
    )
    (net (code "19") (name "Net-(JP2-Pad1)") (class "Default")
      (node (ref "JP2") (pin "1") (pinfunction "1_1") (pintype "passive"))
      (node (ref "JP2") (pin "2") (pinfunction "2_2") (pintype "passive"))
      (node (ref "JP2") (pin "3") (pinfunction "3_3") (pintype "passive"))
      (node (ref "JP2") (pin "4") (pinfunction "4_4") (pintype "passive"))
      (node (ref "JP2") (pin "5") (pinfunction "5_5") (pintype "passive"))
      (node (ref "JP2") (pin "6") (pinfunction "6_6") (pintype "passive"))
      (node (ref "JP2") (pin "7") (pinfunction "7_7") (pintype "passive"))
      (node (ref "JP2") (pin "8") (pinfunction "8_8") (pintype "passive"))
    )
    (net (code "20") (name "Net-(JP3-Pad1)") (class "Default")
      (node (ref "JP3") (pin "1") (pinfunction "1_1") (pintype "passive"))
      (node (ref "JP3") (pin "2") (pinfunction "2_2") (pintype "passive"))
      (node (ref "JP3") (pin "3") (pinfunction "3_3") (pintype "passive"))
      (node (ref "JP3") (pin "4") (pinfunction "4_4") (pintype "passive"))
      (node (ref "JP3") (pin "5") (pinfunction "5_5") (pintype "passive"))
      (node (ref "JP3") (pin "6") (pinfunction "6_6") (pintype "passive"))
      (node (ref "JP3") (pin "7") (pinfunction "7_7") (pintype "passive"))
      (node (ref "JP3") (pin "8") (pinfunction "8_8") (pintype "passive"))
    )
    (net (code "21") (name "Net-(JP4-Pad1)") (class "Default")
      (node (ref "JP4") (pin "1") (pinfunction "1_1") (pintype "passive"))
      (node (ref "JP4") (pin "2") (pinfunction "2_2") (pintype "passive"))
      (node (ref "JP4") (pin "3") (pinfunction "3_3") (pintype "passive"))
      (node (ref "JP4") (pin "4") (pinfunction "4_4") (pintype "passive"))
      (node (ref "JP4") (pin "5") (pinfunction "5_5") (pintype "passive"))
      (node (ref "JP4") (pin "6") (pinfunction "6_6") (pintype "passive"))
      (node (ref "JP4") (pin "7") (pinfunction "7_7") (pintype "passive"))
      (node (ref "JP4") (pin "8") (pinfunction "8_8") (pintype "passive"))
    )
    (net (code "22") (name "Net-(JP5-Pad1)") (class "Default")
      (node (ref "JP5") (pin "1") (pinfunction "1_1") (pintype "passive"))
      (node (ref "JP5") (pin "2") (pinfunction "2_2") (pintype "passive"))
      (node (ref "JP5") (pin "3") (pinfunction "3_3") (pintype "passive"))
      (node (ref "JP5") (pin "4") (pinfunction "4_4") (pintype "passive"))
      (node (ref "JP5") (pin "5") (pinfunction "5_5") (pintype "passive"))
      (node (ref "JP5") (pin "6") (pinfunction "6_6") (pintype "passive"))
      (node (ref "JP5") (pin "7") (pinfunction "7_7") (pintype "passive"))
      (node (ref "JP5") (pin "8") (pinfunction "8_8") (pintype "passive"))
    )
    (net (code "23") (name "Net-(JP6-Pad1)") (class "Default")
      (node (ref "JP6") (pin "1") (pinfunction "1_1") (pintype "passive"))
      (node (ref "JP6") (pin "2") (pinfunction "2_2") (pintype "passive"))
      (node (ref "JP6") (pin "3") (pinfunction "3_3") (pintype "passive"))
      (node (ref "JP6") (pin "4") (pinfunction "4_4") (pintype "passive"))
      (node (ref "JP6") (pin "5") (pinfunction "5_5") (pintype "passive"))
      (node (ref "JP6") (pin "6") (pinfunction "6_6") (pintype "passive"))
      (node (ref "JP6") (pin "7") (pinfunction "7_7") (pintype "passive"))
      (node (ref "JP6") (pin "8") (pinfunction "8_8") (pintype "passive"))
    )
    (net (code "24") (name "Net-(JP7-Pad1)") (class "Default")
      (node (ref "JP7") (pin "1") (pinfunction "1_1") (pintype "passive"))
      (node (ref "JP7") (pin "2") (pinfunction "2_2") (pintype "passive"))
      (node (ref "JP7") (pin "3") (pinfunction "3_3") (pintype "passive"))
      (node (ref "JP7") (pin "4") (pinfunction "4_4") (pintype "passive"))
      (node (ref "JP7") (pin "5") (pinfunction "5_5") (pintype "passive"))
      (node (ref "JP7") (pin "6") (pinfunction "6_6") (pintype "passive"))
      (node (ref "JP7") (pin "7") (pinfunction "7_7") (pintype "passive"))
      (node (ref "JP7") (pin "8") (pinfunction "8_8") (pintype "passive"))
    )
    (net (code "25") (name "Net-(JP8-Pad1)") (class "Default")
      (node (ref "JP8") (pin "1") (pinfunction "1_1") (pintype "passive"))
      (node (ref "JP8") (pin "2") (pinfunction "2_2") (pintype "passive"))
      (node (ref "JP8") (pin "3") (pinfunction "3_3") (pintype "passive"))
      (node (ref "JP8") (pin "4") (pinfunction "4_4") (pintype "passive"))
      (node (ref "JP8") (pin "5") (pinfunction "5_5") (pintype "passive"))
      (node (ref "JP8") (pin "6") (pinfunction "6_6") (pintype "passive"))
      (node (ref "JP8") (pin "7") (pinfunction "7_7") (pintype "passive"))
      (node (ref "JP8") (pin "8") (pinfunction "8_8") (pintype "passive"))
    )
    (net (code "26") (name "Net-(JP9-Pad1)") (class "Default")
      (node (ref "JP9") (pin "1") (pinfunction "1_1") (pintype "passive"))
      (node (ref "JP9") (pin "2") (pinfunction "2_2") (pintype "passive"))
      (node (ref "JP9") (pin "3") (pinfunction "3_3") (pintype "passive"))
      (node (ref "JP9") (pin "4") (pinfunction "4_4") (pintype "passive"))
      (node (ref "JP9") (pin "5") (pinfunction "5_5") (pintype "passive"))
      (node (ref "JP9") (pin "6") (pinfunction "6_6") (pintype "passive"))
      (node (ref "JP9") (pin "7") (pinfunction "7_7") (pintype "passive"))
      (node (ref "JP9") (pin "8") (pinfunction "8_8") (pintype "passive"))
    )
    (net (code "27") (name "Net-(JP10-Pad1)") (class "Default")
      (node (ref "JP10") (pin "1") (pinfunction "1_1") (pintype "passive"))
      (node (ref "JP10") (pin "2") (pinfunction "2_2") (pintype "passive"))
      (node (ref "JP10") (pin "3") (pinfunction "3_3") (pintype "passive"))
      (node (ref "JP10") (pin "4") (pinfunction "4_4") (pintype "passive"))
      (node (ref "JP10") (pin "5") (pinfunction "5_5") (pintype "passive"))
      (node (ref "JP10") (pin "6") (pinfunction "6_6") (pintype "passive"))
      (node (ref "JP10") (pin "7") (pinfunction "7_7") (pintype "passive"))
      (node (ref "JP10") (pin "8") (pinfunction "8_8") (pintype "passive"))
    )
    (net (code "28") (name "Net-(JP11-Pad1)") (class "Default")
      (node (ref "JP11") (pin "1") (pinfunction "1_1") (pintype "passive"))
      (node (ref "JP11") (pin "2") (pinfunction "2_2") (pintype "passive"))
      (node (ref "JP11") (pin "3") (pinfunction "3_3") (pintype "passive"))
      (node (ref "JP11") (pin "4") (pinfunction "4_4") (pintype "passive"))
      (node (ref "JP11") (pin "5") (pinfunction "5_5") (pintype "passive"))
      (node (ref "JP11") (pin "6") (pinfunction "6_6") (pintype "passive"))
      (node (ref "JP11") (pin "7") (pinfunction "7_7") (pintype "passive"))
      (node (ref "JP11") (pin "8") (pinfunction "8_8") (pintype "passive"))
    )
    (net (code "29") (name "Net-(JP12-Pad1)") (class "Default")
      (node (ref "JP12") (pin "1") (pinfunction "1_1") (pintype "passive"))
      (node (ref "JP12") (pin "2") (pinfunction "2_2") (pintype "passive"))
      (node (ref "JP12") (pin "3") (pinfunction "3_3") (pintype "passive"))
      (node (ref "JP12") (pin "4") (pinfunction "4_4") (pintype "passive"))
      (node (ref "JP12") (pin "5") (pinfunction "5_5") (pintype "passive"))
      (node (ref "JP12") (pin "6") (pinfunction "6_6") (pintype "passive"))
      (node (ref "JP12") (pin "7") (pinfunction "7_7") (pintype "passive"))
      (node (ref "JP12") (pin "8") (pinfunction "8_8") (pintype "passive"))
    )
    (net (code "30") (name "Net-(JP13-Pad1)") (class "Default")
      (node (ref "JP13") (pin "1") (pinfunction "1_1") (pintype "passive"))
      (node (ref "JP13") (pin "2") (pinfunction "2_2") (pintype "passive"))
      (node (ref "JP13") (pin "3") (pinfunction "3_3") (pintype "passive"))
      (node (ref "JP13") (pin "4") (pinfunction "4_4") (pintype "passive"))
      (node (ref "JP13") (pin "5") (pinfunction "5_5") (pintype "passive"))
      (node (ref "JP13") (pin "6") (pinfunction "6_6") (pintype "passive"))
      (node (ref "JP13") (pin "7") (pinfunction "7_7") (pintype "passive"))
      (node (ref "JP13") (pin "8") (pinfunction "8_8") (pintype "passive"))
    )
    (net (code "31") (name "Net-(JP14-Pad1)") (class "Default")
      (node (ref "JP14") (pin "1") (pinfunction "1_1") (pintype "passive"))
      (node (ref "JP14") (pin "2") (pinfunction "2_2") (pintype "passive"))
      (node (ref "JP14") (pin "3") (pinfunction "3_3") (pintype "passive"))
      (node (ref "JP14") (pin "4") (pinfunction "4_4") (pintype "passive"))
      (node (ref "JP14") (pin "5") (pinfunction "5_5") (pintype "passive"))
      (node (ref "JP14") (pin "6") (pinfunction "6_6") (pintype "passive"))
      (node (ref "JP14") (pin "7") (pinfunction "7_7") (pintype "passive"))
      (node (ref "JP14") (pin "8") (pinfunction "8_8") (pintype "passive"))
    )
    (net (code "32") (name "Net-(JP15-Pad1)") (class "Default")
      (node (ref "JP15") (pin "1") (pinfunction "1_1") (pintype "passive"))
      (node (ref "JP15") (pin "2") (pinfunction "2_2") (pintype "passive"))
      (node (ref "JP15") (pin "3") (pinfunction "3_3") (pintype "passive"))
      (node (ref "JP15") (pin "4") (pinfunction "4_4") (pintype "passive"))
      (node (ref "JP15") (pin "5") (pinfunction "5_5") (pintype "passive"))
      (node (ref "JP15") (pin "6") (pinfunction "6_6") (pintype "passive"))
      (node (ref "JP15") (pin "7") (pinfunction "7_7") (pintype "passive"))
      (node (ref "JP15") (pin "8") (pinfunction "8_8") (pintype "passive"))
    )
    (net (code "33") (name "Net-(JP16-Pad1)") (class "Default")
      (node (ref "JP16") (pin "1") (pinfunction "1_1") (pintype "passive"))
      (node (ref "JP16") (pin "2") (pinfunction "2_2") (pintype "passive"))
      (node (ref "JP16") (pin "3") (pinfunction "3_3") (pintype "passive"))
      (node (ref "JP16") (pin "4") (pinfunction "4_4") (pintype "passive"))
      (node (ref "JP16") (pin "5") (pinfunction "5_5") (pintype "passive"))
      (node (ref "JP16") (pin "6") (pinfunction "6_6") (pintype "passive"))
      (node (ref "JP16") (pin "7") (pinfunction "7_7") (pintype "passive"))
      (node (ref "JP16") (pin "8") (pinfunction "8_8") (pintype "passive"))
    )
    (net (code "34") (name "Net-(JP17-Pad1)") (class "Default")
      (node (ref "JP17") (pin "1") (pinfunction "1_1") (pintype "passive"))
      (node (ref "JP17") (pin "2") (pinfunction "2_2") (pintype "passive"))
      (node (ref "JP17") (pin "3") (pinfunction "3_3") (pintype "passive"))
      (node (ref "JP17") (pin "4") (pinfunction "4_4") (pintype "passive"))
      (node (ref "JP17") (pin "5") (pinfunction "5_5") (pintype "passive"))
      (node (ref "JP17") (pin "6") (pinfunction "6_6") (pintype "passive"))
      (node (ref "JP17") (pin "7") (pinfunction "7_7") (pintype "passive"))
      (node (ref "JP17") (pin "8") (pinfunction "8_8") (pintype "passive"))
    )
    (net (code "35") (name "Net-(JP18-Pad1)") (class "Default")
      (node (ref "JP18") (pin "1") (pinfunction "1_1") (pintype "passive"))
      (node (ref "JP18") (pin "2") (pinfunction "2_2") (pintype "passive"))
      (node (ref "JP18") (pin "3") (pinfunction "3_3") (pintype "passive"))
      (node (ref "JP18") (pin "4") (pinfunction "4_4") (pintype "passive"))
      (node (ref "JP18") (pin "5") (pinfunction "5_5") (pintype "passive"))
      (node (ref "JP18") (pin "6") (pinfunction "6_6") (pintype "passive"))
      (node (ref "JP18") (pin "7") (pinfunction "7_7") (pintype "passive"))
      (node (ref "JP18") (pin "8") (pinfunction "8_8") (pintype "passive"))
    )
    (net (code "36") (name "Net-(JP19-Pad1)") (class "Default")
      (node (ref "JP19") (pin "1") (pinfunction "1_1") (pintype "passive"))
      (node (ref "JP19") (pin "2") (pinfunction "2_2") (pintype "passive"))
      (node (ref "JP19") (pin "3") (pinfunction "3_3") (pintype "passive"))
      (node (ref "JP19") (pin "4") (pinfunction "4_4") (pintype "passive"))
      (node (ref "JP19") (pin "5") (pinfunction "5_5") (pintype "passive"))
      (node (ref "JP19") (pin "6") (pinfunction "6_6") (pintype "passive"))
      (node (ref "JP19") (pin "7") (pinfunction "7_7") (pintype "passive"))
      (node (ref "JP19") (pin "8") (pinfunction "8_8") (pintype "passive"))
    )
    (net (code "37") (name "Net-(JP20-Pad1)") (class "Default")
      (node (ref "JP20") (pin "1") (pinfunction "1_1") (pintype "passive"))
      (node (ref "JP20") (pin "2") (pinfunction "2_2") (pintype "passive"))
      (node (ref "JP20") (pin "3") (pinfunction "3_3") (pintype "passive"))
      (node (ref "JP20") (pin "4") (pinfunction "4_4") (pintype "passive"))
      (node (ref "JP20") (pin "5") (pinfunction "5_5") (pintype "passive"))
      (node (ref "JP20") (pin "6") (pinfunction "6_6") (pintype "passive"))
      (node (ref "JP20") (pin "7") (pinfunction "7_7") (pintype "passive"))
      (node (ref "JP20") (pin "8") (pinfunction "8_8") (pintype "passive"))
    )
    (net (code "38") (name "Net-(JP21-Pad1)") (class "Default")
      (node (ref "JP21") (pin "1") (pinfunction "1_1") (pintype "passive"))
      (node (ref "JP21") (pin "2") (pinfunction "2_2") (pintype "passive"))
      (node (ref "JP21") (pin "3") (pinfunction "3_3") (pintype "passive"))
      (node (ref "JP21") (pin "4") (pinfunction "4_4") (pintype "passive"))
      (node (ref "JP21") (pin "5") (pinfunction "5_5") (pintype "passive"))
      (node (ref "JP21") (pin "6") (pinfunction "6_6") (pintype "passive"))
      (node (ref "JP21") (pin "7") (pinfunction "7_7") (pintype "passive"))
      (node (ref "JP21") (pin "8") (pinfunction "8_8") (pintype "passive"))
    )
    (net (code "39") (name "Net-(JP22-Pad1)") (class "Default")
      (node (ref "JP22") (pin "1") (pinfunction "1_1") (pintype "passive"))
      (node (ref "JP22") (pin "2") (pinfunction "2_2") (pintype "passive"))
      (node (ref "JP22") (pin "3") (pinfunction "3_3") (pintype "passive"))
      (node (ref "JP22") (pin "4") (pinfunction "4_4") (pintype "passive"))
      (node (ref "JP22") (pin "5") (pinfunction "5_5") (pintype "passive"))
      (node (ref "JP22") (pin "6") (pinfunction "6_6") (pintype "passive"))
      (node (ref "JP22") (pin "7") (pinfunction "7_7") (pintype "passive"))
      (node (ref "JP22") (pin "8") (pinfunction "8_8") (pintype "passive"))
    )
    (net (code "40") (name "Net-(JP23-Pad1)") (class "Default")
      (node (ref "JP23") (pin "1") (pinfunction "1_1") (pintype "passive"))
      (node (ref "JP23") (pin "2") (pinfunction "2_2") (pintype "passive"))
      (node (ref "JP23") (pin "3") (pinfunction "3_3") (pintype "passive"))
      (node (ref "JP23") (pin "4") (pinfunction "4_4") (pintype "passive"))
      (node (ref "JP23") (pin "5") (pinfunction "5_5") (pintype "passive"))
      (node (ref "JP23") (pin "6") (pinfunction "6_6") (pintype "passive"))
      (node (ref "JP23") (pin "7") (pinfunction "7_7") (pintype "passive"))
      (node (ref "JP23") (pin "8") (pinfunction "8_8") (pintype "passive"))
    )
    (net (code "41") (name "Net-(JP24-Pad1)") (class "Default")
      (node (ref "JP24") (pin "1") (pinfunction "1_1") (pintype "passive"))
      (node (ref "JP24") (pin "2") (pinfunction "2_2") (pintype "passive"))
      (node (ref "JP24") (pin "3") (pinfunction "3_3") (pintype "passive"))
      (node (ref "JP24") (pin "4") (pinfunction "4_4") (pintype "passive"))
      (node (ref "JP24") (pin "5") (pinfunction "5_5") (pintype "passive"))
      (node (ref "JP24") (pin "6") (pinfunction "6_6") (pintype "passive"))
      (node (ref "JP24") (pin "7") (pinfunction "7_7") (pintype "passive"))
      (node (ref "JP24") (pin "8") (pinfunction "8_8") (pintype "passive"))
    )
    (net (code "42") (name "Net-(JP25-Pad1)") (class "Default")
      (node (ref "JP25") (pin "1") (pinfunction "1_1") (pintype "passive"))
      (node (ref "JP25") (pin "2") (pinfunction "2_2") (pintype "passive"))
      (node (ref "JP25") (pin "3") (pinfunction "3_3") (pintype "passive"))
      (node (ref "JP25") (pin "4") (pinfunction "4_4") (pintype "passive"))
      (node (ref "JP25") (pin "5") (pinfunction "5_5") (pintype "passive"))
      (node (ref "JP25") (pin "6") (pinfunction "6_6") (pintype "passive"))
      (node (ref "JP25") (pin "7") (pinfunction "7_7") (pintype "passive"))
      (node (ref "JP25") (pin "8") (pinfunction "8_8") (pintype "passive"))
    )
    (net (code "43") (name "Net-(JP26-Pad1)") (class "Default")
      (node (ref "JP26") (pin "1") (pinfunction "1_1") (pintype "passive"))
      (node (ref "JP26") (pin "2") (pinfunction "2_2") (pintype "passive"))
      (node (ref "JP26") (pin "3") (pinfunction "3_3") (pintype "passive"))
      (node (ref "JP26") (pin "4") (pinfunction "4_4") (pintype "passive"))
      (node (ref "JP26") (pin "5") (pinfunction "5_5") (pintype "passive"))
      (node (ref "JP26") (pin "6") (pinfunction "6_6") (pintype "passive"))
      (node (ref "JP26") (pin "7") (pinfunction "7_7") (pintype "passive"))
      (node (ref "JP26") (pin "8") (pinfunction "8_8") (pintype "passive"))
    )
    (net (code "44") (name "Net-(JP27-Pad1)") (class "Default")
      (node (ref "JP27") (pin "1") (pinfunction "1_1") (pintype "passive"))
      (node (ref "JP27") (pin "2") (pinfunction "2_2") (pintype "passive"))
      (node (ref "JP27") (pin "3") (pinfunction "3_3") (pintype "passive"))
      (node (ref "JP27") (pin "4") (pinfunction "4_4") (pintype "passive"))
      (node (ref "JP27") (pin "5") (pinfunction "5_5") (pintype "passive"))
      (node (ref "JP27") (pin "6") (pinfunction "6_6") (pintype "passive"))
      (node (ref "JP27") (pin "7") (pinfunction "7_7") (pintype "passive"))
      (node (ref "JP27") (pin "8") (pinfunction "8_8") (pintype "passive"))
    )
    (net (code "45") (name "Net-(JP28-Pad1)") (class "Default")
      (node (ref "JP28") (pin "1") (pinfunction "1_1") (pintype "passive"))
      (node (ref "JP28") (pin "2") (pinfunction "2_2") (pintype "passive"))
      (node (ref "JP28") (pin "3") (pinfunction "3_3") (pintype "passive"))
      (node (ref "JP28") (pin "4") (pinfunction "4_4") (pintype "passive"))
      (node (ref "JP28") (pin "5") (pinfunction "5_5") (pintype "passive"))
      (node (ref "JP28") (pin "6") (pinfunction "6_6") (pintype "passive"))
      (node (ref "JP28") (pin "7") (pinfunction "7_7") (pintype "passive"))
      (node (ref "JP28") (pin "8") (pinfunction "8_8") (pintype "passive"))
    )
    (net (code "46") (name "Net-(JP29-Pad1)") (class "Default")
      (node (ref "JP29") (pin "1") (pinfunction "1_1") (pintype "passive"))
      (node (ref "JP29") (pin "2") (pinfunction "2_2") (pintype "passive"))
      (node (ref "JP29") (pin "3") (pinfunction "3_3") (pintype "passive"))
      (node (ref "JP29") (pin "4") (pinfunction "4_4") (pintype "passive"))
      (node (ref "JP29") (pin "5") (pinfunction "5_5") (pintype "passive"))
      (node (ref "JP29") (pin "6") (pinfunction "6_6") (pintype "passive"))
      (node (ref "JP29") (pin "7") (pinfunction "7_7") (pintype "passive"))
      (node (ref "JP29") (pin "8") (pinfunction "8_8") (pintype "passive"))
    )
    (net (code "47") (name "Net-(JP30-Pad1)") (class "Default")
      (node (ref "JP30") (pin "1") (pinfunction "1_1") (pintype "passive"))
      (node (ref "JP30") (pin "2") (pinfunction "2_2") (pintype "passive"))
      (node (ref "JP30") (pin "3") (pinfunction "3_3") (pintype "passive"))
      (node (ref "JP30") (pin "4") (pinfunction "4_4") (pintype "passive"))
      (node (ref "JP30") (pin "5") (pinfunction "5_5") (pintype "passive"))
      (node (ref "JP30") (pin "6") (pinfunction "6_6") (pintype "passive"))
      (node (ref "JP30") (pin "7") (pinfunction "7_7") (pintype "passive"))
      (node (ref "JP30") (pin "8") (pinfunction "8_8") (pintype "passive"))
    )
    (net (code "48") (name "Net-(JP35-Pad1)") (class "Default")
      (node (ref "JP35") (pin "1") (pinfunction "1_1") (pintype "passive"))
      (node (ref "JP35") (pin "2") (pinfunction "2_2") (pintype "passive"))
      (node (ref "JP35") (pin "3") (pinfunction "3_3") (pintype "passive"))
      (node (ref "JP35") (pin "4") (pinfunction "4_4") (pintype "passive"))
      (node (ref "JP35") (pin "5") (pinfunction "5_5") (pintype "passive"))
      (node (ref "JP35") (pin "6") (pinfunction "6_6") (pintype "passive"))
      (node (ref "JP35") (pin "7") (pinfunction "7_7") (pintype "passive"))
      (node (ref "JP35") (pin "8") (pinfunction "8_8") (pintype "passive"))
    )
    (net (code "49") (name "Net-(JP36-Pad1)") (class "Default")
      (node (ref "JP36") (pin "1") (pinfunction "1_1") (pintype "passive"))
      (node (ref "JP36") (pin "2") (pinfunction "2_2") (pintype "passive"))
      (node (ref "JP36") (pin "3") (pinfunction "3_3") (pintype "passive"))
      (node (ref "JP36") (pin "4") (pinfunction "4_4") (pintype "passive"))
      (node (ref "JP36") (pin "5") (pinfunction "5_5") (pintype "passive"))
      (node (ref "JP36") (pin "6") (pinfunction "6_6") (pintype "passive"))
      (node (ref "JP36") (pin "7") (pinfunction "7_7") (pintype "passive"))
      (node (ref "JP36") (pin "8") (pinfunction "8_8") (pintype "passive"))
    )
    (net (code "50") (name "Net-(X1-ADC)") (class "Default")
      (node (ref "J7") (pin "1") (pinfunction "1_1") (pintype "passive"))
      (node (ref "J7") (pin "2") (pinfunction "2_2") (pintype "passive"))
      (node (ref "J7") (pin "3") (pinfunction "3_3") (pintype "passive"))
      (node (ref "J7") (pin "4") (pinfunction "4_4") (pintype "passive"))
      (node (ref "J7") (pin "5") (pinfunction "5_5") (pintype "passive"))
      (node (ref "J7") (pin "6") (pinfunction "6_6") (pintype "passive"))
      (node (ref "X1") (pin "2") (pinfunction "ADC_2") (pintype "passive"))
    )
    (net (code "51") (name "Net-(X1-CH_PD)") (class "Default")
      (node (ref "J6") (pin "1") (pinfunction "1_1") (pintype "passive"))
      (node (ref "J6") (pin "2") (pinfunction "2_2") (pintype "passive"))
      (node (ref "J6") (pin "3") (pinfunction "3_3") (pintype "passive"))
      (node (ref "J6") (pin "4") (pinfunction "4_4") (pintype "passive"))
      (node (ref "J6") (pin "5") (pinfunction "5_5") (pintype "passive"))
      (node (ref "J6") (pin "6") (pinfunction "6_6") (pintype "passive"))
      (node (ref "X1") (pin "3") (pinfunction "CH_PD_3") (pintype "input"))
    )
    (net (code "52") (name "Net-(X1-GPIO0)") (class "Default")
      (node (ref "J11") (pin "1") (pinfunction "1_1") (pintype "passive"))
      (node (ref "J11") (pin "2") (pinfunction "2_2") (pintype "passive"))
      (node (ref "J11") (pin "3") (pinfunction "3_3") (pintype "passive"))
      (node (ref "J11") (pin "4") (pinfunction "4_4") (pintype "passive"))
      (node (ref "J11") (pin "5") (pinfunction "5_5") (pintype "passive"))
      (node (ref "J11") (pin "6") (pinfunction "6_6") (pintype "passive"))
      (node (ref "X1") (pin "12") (pinfunction "GPIO0_12") (pintype "bidirectional"))
    )
    (net (code "53") (name "Net-(X1-GPIO2)") (class "Default")
      (node (ref "J10") (pin "1") (pinfunction "1_1") (pintype "passive"))
      (node (ref "J10") (pin "2") (pinfunction "2_2") (pintype "passive"))
      (node (ref "J10") (pin "3") (pinfunction "3_3") (pintype "passive"))
      (node (ref "J10") (pin "4") (pinfunction "4_4") (pintype "passive"))
      (node (ref "J10") (pin "5") (pinfunction "5_5") (pintype "passive"))
      (node (ref "J10") (pin "6") (pinfunction "6_6") (pintype "passive"))
      (node (ref "X1") (pin "11") (pinfunction "GPIO2_11") (pintype "bidirectional"))
    )
    (net (code "54") (name "Net-(X1-GPIO4)") (class "Default")
      (node (ref "J12") (pin "1") (pinfunction "1_1") (pintype "passive"))
      (node (ref "J12") (pin "2") (pinfunction "2_2") (pintype "passive"))
      (node (ref "J12") (pin "3") (pinfunction "3_3") (pintype "passive"))
      (node (ref "J12") (pin "4") (pinfunction "4_4") (pintype "passive"))
      (node (ref "J12") (pin "5") (pinfunction "5_5") (pintype "passive"))
      (node (ref "J12") (pin "6") (pinfunction "6_6") (pintype "passive"))
      (node (ref "X1") (pin "13") (pinfunction "GPIO4_13") (pintype "bidirectional"))
    )
    (net (code "55") (name "Net-(X1-GPIO5)") (class "Default")
      (node (ref "J13") (pin "1") (pinfunction "1_1") (pintype "passive"))
      (node (ref "J13") (pin "2") (pinfunction "2_2") (pintype "passive"))
      (node (ref "J13") (pin "3") (pinfunction "3_3") (pintype "passive"))
      (node (ref "J13") (pin "4") (pinfunction "4_4") (pintype "passive"))
      (node (ref "J13") (pin "5") (pinfunction "5_5") (pintype "passive"))
      (node (ref "J13") (pin "6") (pinfunction "6_6") (pintype "passive"))
      (node (ref "X1") (pin "14") (pinfunction "GPIO5_14") (pintype "bidirectional"))
    )
    (net (code "56") (name "Net-(X1-GPIO12)") (class "Default")
      (node (ref "J3") (pin "1") (pinfunction "1_1") (pintype "passive"))
      (node (ref "J3") (pin "2") (pinfunction "2_2") (pintype "passive"))
      (node (ref "J3") (pin "3") (pinfunction "3_3") (pintype "passive"))
      (node (ref "J3") (pin "4") (pinfunction "4_4") (pintype "passive"))
      (node (ref "J3") (pin "5") (pinfunction "5_5") (pintype "passive"))
      (node (ref "J3") (pin "6") (pinfunction "6_6") (pintype "passive"))
      (node (ref "X1") (pin "6") (pinfunction "GPIO12_6") (pintype "bidirectional"))
    )
    (net (code "57") (name "Net-(X1-GPIO13)") (class "Default")
      (node (ref "J2") (pin "1") (pinfunction "1_1") (pintype "passive"))
      (node (ref "J2") (pin "2") (pinfunction "2_2") (pintype "passive"))
      (node (ref "J2") (pin "3") (pinfunction "3_3") (pintype "passive"))
      (node (ref "J2") (pin "4") (pinfunction "4_4") (pintype "passive"))
      (node (ref "J2") (pin "5") (pinfunction "5_5") (pintype "passive"))
      (node (ref "J2") (pin "6") (pinfunction "6_6") (pintype "passive"))
      (node (ref "X1") (pin "7") (pinfunction "GPIO13_7") (pintype "bidirectional"))
    )
    (net (code "58") (name "Net-(X1-GPIO14)") (class "Default")
      (node (ref "J4") (pin "1") (pinfunction "1_1") (pintype "passive"))
      (node (ref "J4") (pin "2") (pinfunction "2_2") (pintype "passive"))
      (node (ref "J4") (pin "3") (pinfunction "3_3") (pintype "passive"))
      (node (ref "J4") (pin "4") (pinfunction "4_4") (pintype "passive"))
      (node (ref "J4") (pin "5") (pinfunction "5_5") (pintype "passive"))
      (node (ref "J4") (pin "6") (pinfunction "6_6") (pintype "passive"))
      (node (ref "X1") (pin "5") (pinfunction "GPIO14_5") (pintype "bidirectional"))
    )
    (net (code "59") (name "Net-(X1-GPIO15)") (class "Default")
      (node (ref "J9") (pin "1") (pinfunction "1_1") (pintype "passive"))
      (node (ref "J9") (pin "2") (pinfunction "2_2") (pintype "passive"))
      (node (ref "J9") (pin "3") (pinfunction "3_3") (pintype "passive"))
      (node (ref "J9") (pin "4") (pinfunction "4_4") (pintype "passive"))
      (node (ref "J9") (pin "5") (pinfunction "5_5") (pintype "passive"))
      (node (ref "J9") (pin "6") (pinfunction "6_6") (pintype "passive"))
      (node (ref "X1") (pin "10") (pinfunction "GPIO15_10") (pintype "bidirectional"))
    )
    (net (code "60") (name "Net-(X1-GPIO16)") (class "Default")
      (node (ref "J5") (pin "1") (pinfunction "1_1") (pintype "passive"))
      (node (ref "J5") (pin "2") (pinfunction "2_2") (pintype "passive"))
      (node (ref "J5") (pin "3") (pinfunction "3_3") (pintype "passive"))
      (node (ref "J5") (pin "4") (pinfunction "4_4") (pintype "passive"))
      (node (ref "J5") (pin "5") (pinfunction "5_5") (pintype "passive"))
      (node (ref "J5") (pin "6") (pinfunction "6_6") (pintype "passive"))
      (node (ref "X1") (pin "4") (pinfunction "GPIO16_4") (pintype "bidirectional"))
    )
    (net (code "61") (name "Net-(X1-RESET)") (class "Default")
      (node (ref "J8") (pin "1") (pinfunction "1_1") (pintype "passive"))
      (node (ref "J8") (pin "2") (pinfunction "2_2") (pintype "passive"))
      (node (ref "J8") (pin "3") (pinfunction "3_3") (pintype "passive"))
      (node (ref "J8") (pin "4") (pinfunction "4_4") (pintype "passive"))
      (node (ref "J8") (pin "5") (pinfunction "5_5") (pintype "passive"))
      (node (ref "J8") (pin "6") (pinfunction "6_6") (pintype "passive"))
      (node (ref "X1") (pin "1") (pinfunction "RESET_1") (pintype "input"))
    )
    (net (code "62") (name "Net-(X1-RXD)") (class "Default")
      (node (ref "JP37") (pin "4") (pinfunction "4_4") (pintype "passive"))
      (node (ref "X1") (pin "15") (pinfunction "RXD_15") (pintype "input"))
    )
    (net (code "63") (name "Net-(X1-TXD)") (class "Default")
      (node (ref "JP37") (pin "5") (pinfunction "5_5") (pintype "passive"))
      (node (ref "X1") (pin "16") (pinfunction "TXD_16") (pintype "output"))
    )
    (net (code "64") (name "VCC") (class "Default")
      (node (ref "DC1") (pin "1") (pinfunction "VIN_1") (pintype "passive"))
      (node (ref "J1") (pin "1") (pinfunction "1_1") (pintype "passive"))
      (node (ref "J24") (pin "1") (pinfunction "1_1") (pintype "passive"))
      (node (ref "JP37") (pin "2") (pinfunction "2_2") (pintype "passive"))
      (node (ref "U1") (pin "1") (pinfunction "IN_1") (pintype "input"))
      (node (ref "U1") (pin "3") (pinfunction "EN_3") (pintype "input"))
      (node (ref "X2") (pin "VBUS") (pinfunction "VBUS_VBUS") (pintype "power_in"))
    )
    (net (code "65") (name "VDD") (class "Default")
      (node (ref "DC1") (pin "3") (pinfunction "VOUT_3") (pintype "passive"))
      (node (ref "J15") (pin "1") (pinfunction "1_1") (pintype "passive"))
      (node (ref "J15") (pin "10") (pinfunction "10_10") (pintype "passive"))
      (node (ref "J15") (pin "11") (pinfunction "11_11") (pintype "passive"))
      (node (ref "J15") (pin "2") (pinfunction "2_2") (pintype "passive"))
      (node (ref "J15") (pin "3") (pinfunction "3_3") (pintype "passive"))
      (node (ref "J15") (pin "4") (pinfunction "4_4") (pintype "passive"))
      (node (ref "J15") (pin "5") (pinfunction "5_5") (pintype "passive"))
      (node (ref "J15") (pin "6") (pinfunction "6_6") (pintype "passive"))
      (node (ref "J15") (pin "7") (pinfunction "7_7") (pintype "passive"))
      (node (ref "J15") (pin "8") (pinfunction "8_8") (pintype "passive"))
      (node (ref "J15") (pin "9") (pinfunction "9_9") (pintype "passive"))
      (node (ref "J17") (pin "1") (pinfunction "1_1") (pintype "passive"))
      (node (ref "J17") (pin "10") (pinfunction "10_10") (pintype "passive"))
      (node (ref "J17") (pin "11") (pinfunction "11_11") (pintype "passive"))
      (node (ref "J17") (pin "2") (pinfunction "2_2") (pintype "passive"))
      (node (ref "J17") (pin "3") (pinfunction "3_3") (pintype "passive"))
      (node (ref "J17") (pin "4") (pinfunction "4_4") (pintype "passive"))
      (node (ref "J17") (pin "5") (pinfunction "5_5") (pintype "passive"))
      (node (ref "J17") (pin "6") (pinfunction "6_6") (pintype "passive"))
      (node (ref "J17") (pin "7") (pinfunction "7_7") (pintype "passive"))
      (node (ref "J17") (pin "8") (pinfunction "8_8") (pintype "passive"))
      (node (ref "J17") (pin "9") (pinfunction "9_9") (pintype "passive"))
      (node (ref "JP33") (pin "1") (pinfunction "1_1") (pintype "passive"))
      (node (ref "JP33") (pin "10") (pinfunction "10_10") (pintype "passive"))
      (node (ref "JP33") (pin "11") (pinfunction "11_11") (pintype "passive"))
      (node (ref "JP33") (pin "12") (pinfunction "12_12") (pintype "passive"))
      (node (ref "JP33") (pin "2") (pinfunction "2_2") (pintype "passive"))
      (node (ref "JP33") (pin "3") (pinfunction "3_3") (pintype "passive"))
      (node (ref "JP33") (pin "4") (pinfunction "4_4") (pintype "passive"))
      (node (ref "JP33") (pin "5") (pinfunction "5_5") (pintype "passive"))
      (node (ref "JP33") (pin "6") (pinfunction "6_6") (pintype "passive"))
      (node (ref "JP33") (pin "7") (pinfunction "7_7") (pintype "passive"))
      (node (ref "JP33") (pin "8") (pinfunction "8_8") (pintype "passive"))
      (node (ref "JP33") (pin "9") (pinfunction "9_9") (pintype "passive"))
      (node (ref "JP34") (pin "1") (pinfunction "1_1") (pintype "passive"))
      (node (ref "JP34") (pin "10") (pinfunction "10_10") (pintype "passive"))
      (node (ref "JP34") (pin "11") (pinfunction "11_11") (pintype "passive"))
      (node (ref "JP34") (pin "12") (pinfunction "12_12") (pintype "passive"))
      (node (ref "JP34") (pin "2") (pinfunction "2_2") (pintype "passive"))
      (node (ref "JP34") (pin "3") (pinfunction "3_3") (pintype "passive"))
      (node (ref "JP34") (pin "4") (pinfunction "4_4") (pintype "passive"))
      (node (ref "JP34") (pin "5") (pinfunction "5_5") (pintype "passive"))
      (node (ref "JP34") (pin "6") (pinfunction "6_6") (pintype "passive"))
      (node (ref "JP34") (pin "7") (pinfunction "7_7") (pintype "passive"))
      (node (ref "JP34") (pin "8") (pinfunction "8_8") (pintype "passive"))
      (node (ref "JP34") (pin "9") (pinfunction "9_9") (pintype "passive"))
      (node (ref "U1") (pin "5") (pinfunction "OUT_5") (pintype "passive"))
      (node (ref "X1") (pin "8") (pinfunction "VCC_8") (pintype "power_in"))
    )
    (net (code "66") (name "unconnected-(JP37-Pad3)") (class "Default")
      (node (ref "JP37") (pin "3") (pinfunction "3_3") (pintype "passive"))
    )
    (net (code "67") (name "unconnected-(U1-BP-Pad4)") (class "Default")
      (node (ref "U1") (pin "4") (pinfunction "BP_4") (pintype "input"))
    )
    (net (code "68") (name "unconnected-(X1-CLK-Pad20)") (class "Default")
      (node (ref "X1") (pin "20") (pinfunction "CLK_20") (pintype "bidirectional"))
    )
    (net (code "69") (name "unconnected-(X1-CS-Pad17)") (class "Default")
      (node (ref "X1") (pin "17") (pinfunction "CS_17") (pintype "bidirectional"))
    )
    (net (code "70") (name "unconnected-(X1-DI-Pad21)") (class "Default")
      (node (ref "X1") (pin "21") (pinfunction "DI_21") (pintype "bidirectional"))
    )
    (net (code "71") (name "unconnected-(X1-DO-Pad18)") (class "Default")
      (node (ref "X1") (pin "18") (pinfunction "DO_18") (pintype "bidirectional"))
    )
    (net (code "72") (name "unconnected-(X1-GPIO9-Pad22)") (class "Default")
      (node (ref "X1") (pin "22") (pinfunction "GPIO9_22") (pintype "bidirectional"))
    )
    (net (code "73") (name "unconnected-(X1-GPIO10-Pad19)") (class "Default")
      (node (ref "X1") (pin "19") (pinfunction "GPIO10_19") (pintype "bidirectional"))
    )
    (net (code "74") (name "unconnected-(X2-PadD+)") (class "Default")
      (node (ref "X2") (pin "D+") (pinfunction "D+_D+") (pintype "bidirectional"))
    )
    (net (code "75") (name "unconnected-(X2-PadD-)") (class "Default")
      (node (ref "X2") (pin "D-") (pinfunction "D-_D-") (pintype "bidirectional"))
    )
    (net (code "76") (name "unconnected-(X2-PadID)") (class "Default")
      (node (ref "X2") (pin "ID") (pinfunction "ID_ID") (pintype "bidirectional"))
    )
  )
)
